# 3_MotorDriver.net
KiCad netlist of a schematic drawn in Altium Designer
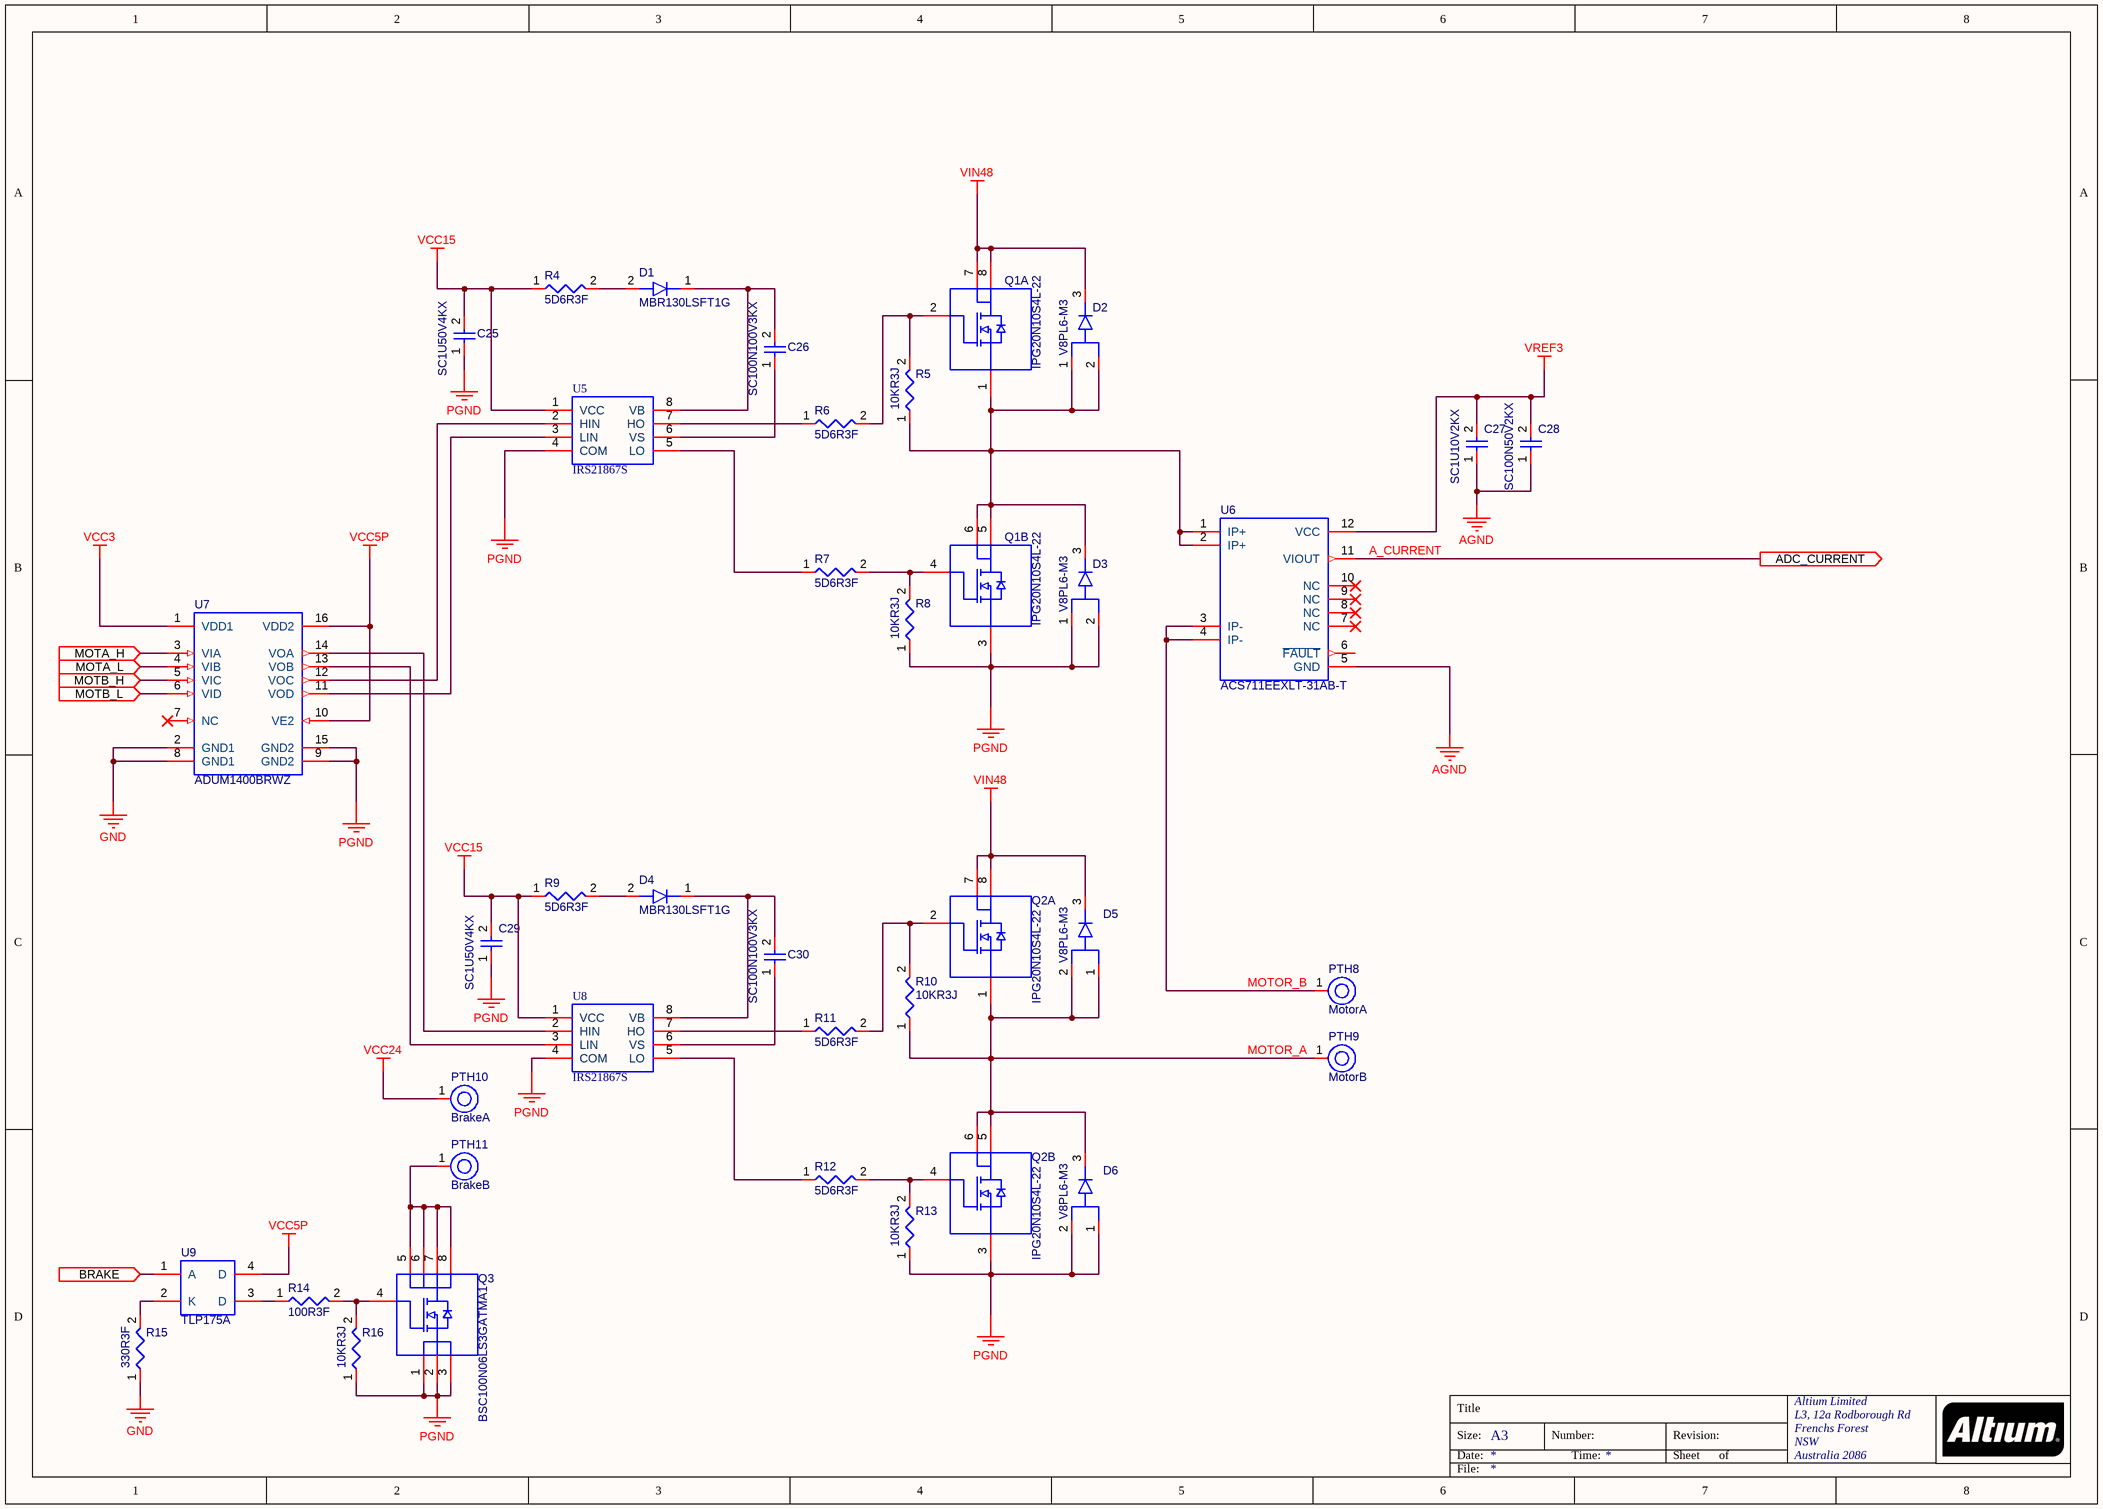
[diagram p0: 3_MotorDriver.SchDoc]

(export (version "E")
  (design (tool "Eeschema 10.0.6"))
  (components
    (comp (ref "C25")
      (value "SC1U50V4KX")
      (footprint "CAPC0805(2012)145_L")
      (description "CAP 1uF 50V ±10% 0805(1610 Metric) Thickness 1.2mm SMD")
      (libsource (lib "PUMAlib") (part "CAP(0805)1UF50V"))
    )
    (comp (ref "C26")
      (value "SC100N100V3KX")
      (footprint "CAPC0603(1608)100_L")
      (description "CAP 100nF 100V ±10% 0603(1608 Metric) Thickness 1mm SMD")
      (libsource (lib "PUMAlib") (part "CAP(0603)100nF100V"))
    )
    (comp (ref "C27")
      (value "SC1U10V2KX")
      (footprint "CAPC0402(1005)60_L")
      (description "CAP 1uF 10V ±10% 0402 (1005 Metric) Thickness 0.6mm SMD")
      (libsource (lib "Schlib") (part "CAP(0402)1UF10V"))
    )
    (comp (ref "C28")
      (value "SC100N50V2KX")
      (footprint "CAPC0402(1005)60_L")
      (description "CAP 100nF 50V ±10% 0402 (1005 Metric) Thickness 0.6mm SMD")
      (libsource (lib "Schlib") (part "CAP(0402)100nF50V"))
    )
    (comp (ref "C29")
      (value "SC1U50V4KX")
      (footprint "CAPC0805(2012)145_L")
      (description "CAP 1uF 50V ±10% 0805(1610 Metric) Thickness 1.2mm SMD")
      (libsource (lib "PUMAlib") (part "CAP(0805)1UF50V"))
    )
    (comp (ref "C30")
      (value "SC100N100V3KX")
      (footprint "CAPC0603(1608)100_L")
      (description "CAP 100nF 100V ±10% 0603(1608 Metric) Thickness 1mm SMD")
      (libsource (lib "PUMAlib") (part "CAP(0603)100nF100V"))
    )
    (comp (ref "D1")
      (value "MBR130LSFT1G")
      (footprint "SOD-123LF")
      (description "1А 30В [SOD-123FL]\r, RoHS, Tape and Reel")
      (fields (field (name "MANUFACTURER") "Rohm"))
      (libsource (lib "PUMAlib") (part "DIOD-MBR130"))
    )
    (comp (ref "D2")
      (value "V8PL6-M3")
      (footprint "DFN442P610X120-3L")
      (libsource (lib "PUMAlib") (part "VISH-V8PL6-M3"))
    )
    (comp (ref "D3")
      (value "V8PL6-M3")
      (footprint "DFN442P610X120-3L")
      (libsource (lib "PUMAlib") (part "VISH-V8PL6-M3"))
    )
    (comp (ref "D4")
      (value "MBR130LSFT1G")
      (footprint "SOD-123LF")
      (description "1А 30В [SOD-123FL]\r, RoHS, Tape and Reel")
      (fields (field (name "MANUFACTURER") "Rohm"))
      (libsource (lib "PUMAlib") (part "DIOD-MBR130"))
    )
    (comp (ref "D5")
      (value "V8PL6-M3")
      (footprint "DFN442P610X120-3L")
      (libsource (lib "PUMAlib") (part "VISH-V8PL6-M3"))
    )
    (comp (ref "D6")
      (value "V8PL6-M3")
      (footprint "DFN442P610X120-3L")
      (libsource (lib "PUMAlib") (part "VISH-V8PL6-M3"))
    )
    (comp (ref "PTH8")
      (value "MotorA")
      (footprint "POWERHOLE-LP")
      (description "1.2mm hole 2mm pad")
      (libsource (lib "PUMAlib") (part "PTH-1D2M"))
    )
    (comp (ref "PTH9")
      (value "MotorB")
      (footprint "POWERHOLE-LP")
      (description "1.2mm hole 2mm pad")
      (libsource (lib "PUMAlib") (part "PTH-1D2M"))
    )
    (comp (ref "PTH10")
      (value "BrakeA")
      (footprint "POWERHOLE-LP")
      (description "1.2mm hole 2mm pad")
      (libsource (lib "PUMAlib") (part "PTH-1D2M"))
    )
    (comp (ref "PTH11")
      (value "BrakeB")
      (footprint "POWERHOLE-LP")
      (description "1.2mm hole 2mm pad")
      (libsource (lib "PUMAlib") (part "PTH-1D2M"))
    )
    (comp (ref "Q1")
      (value "IPG20N10S4L-22")
      (footprint "PG-TDSON-8-4")
      (description "OptiMOS™-T2 Power-Transistor V DS 100 V\r\nR DS(on) max 22\r\nID 20 A")
      (libsource (lib "PUMAlib") (part "INF_IPG20N06S4L-26"))
    )
    (comp (ref "Q2")
      (value "IPG20N10S4L-22")
      (footprint "PG-TDSON-8-4")
      (description "OptiMOS™-T2 Power-Transistor V DS 100 V\r\nR DS(on) max 22\r\nID 20 A")
      (libsource (lib "PUMAlib") (part "INF_IPG20N06S4L-26"))
    )
    (comp (ref "Q3")
      (value "BSC100N06LS3GATMA1")
      (footprint "PG-TDSON-8-1")
      (description "100 V N-Channel NexFET™ Power MOSFETs")
      (libsource (lib "PUMAlib") (part "NEMOS-BSC100N06L"))
    )
    (comp (ref "R4")
      (value "5D6R3F")
      (footprint "RESC0603(1608)_L")
      (description "5.6R 0.1W 1% 0603 (1608 Metric)  SMD")
      (libsource (lib "PUMAlib") (part "RES0(0603)_5R6"))
    )
    (comp (ref "R5")
      (value "10KR3J")
      (footprint "RESC0603(1608)_L")
      (description "10K 0.1W 5% 0603 (1608 Metric)  SMD")
      (libsource (lib "PUMAlib") (part "RES0(0603)_10K"))
    )
    (comp (ref "R6")
      (value "5D6R3F")
      (footprint "RESC0603(1608)_L")
      (description "5.6R 0.1W 1% 0603 (1608 Metric)  SMD")
      (libsource (lib "PUMAlib") (part "RES0(0603)_5R6"))
    )
    (comp (ref "R7")
      (value "5D6R3F")
      (footprint "RESC0603(1608)_L")
      (description "5.6R 0.1W 1% 0603 (1608 Metric)  SMD")
      (libsource (lib "PUMAlib") (part "RES0(0603)_5R6"))
    )
    (comp (ref "R8")
      (value "10KR3J")
      (footprint "RESC0603(1608)_L")
      (description "10K 0.1W 5% 0603 (1608 Metric)  SMD")
      (libsource (lib "PUMAlib") (part "RES0(0603)_10K"))
    )
    (comp (ref "R9")
      (value "5D6R3F")
      (footprint "RESC0603(1608)_L")
      (description "5.6R 0.1W 1% 0603 (1608 Metric)  SMD")
      (libsource (lib "PUMAlib") (part "RES0(0603)_5R6"))
    )
    (comp (ref "R10")
      (value "10KR3J")
      (footprint "RESC0603(1608)_L")
      (description "10K 0.1W 5% 0603 (1608 Metric)  SMD")
      (libsource (lib "PUMAlib") (part "RES0(0603)_10K"))
    )
    (comp (ref "R11")
      (value "5D6R3F")
      (footprint "RESC0603(1608)_L")
      (description "5.6R 0.1W 1% 0603 (1608 Metric)  SMD")
      (libsource (lib "PUMAlib") (part "RES0(0603)_5R6"))
    )
    (comp (ref "R12")
      (value "5D6R3F")
      (footprint "RESC0603(1608)_L")
      (description "5.6R 0.1W 1% 0603 (1608 Metric)  SMD")
      (libsource (lib "PUMAlib") (part "RES0(0603)_5R6"))
    )
    (comp (ref "R13")
      (value "10KR3J")
      (footprint "RESC0603(1608)_L")
      (description "10K 0.1W 5% 0603 (1608 Metric)  SMD")
      (libsource (lib "PUMAlib") (part "RES0(0603)_10K"))
    )
    (comp (ref "R14")
      (value "100R3F")
      (footprint "RESC0603(1608)_L")
      (description "100R 0.1W 1% 0603 (1608 Metric)  SMD")
      (libsource (lib "PUMAlib") (part "RES0(0603)_100R"))
    )
    (comp (ref "R15")
      (value "330R3F")
      (footprint "RESC0603(1608)_L")
      (description "330R 0.1W 1% 0603 (1608 Metric)  SMD")
      (libsource (lib "PUMAlib") (part "RES0(0603)_330R"))
    )
    (comp (ref "R16")
      (value "10KR3J")
      (footprint "RESC0603(1608)_L")
      (description "10K 0.1W 5% 0603 (1608 Metric)  SMD")
      (libsource (lib "PUMAlib") (part "RES0(0603)_10K"))
    )
    (comp (ref "U5")
      (value "IRS21867S")
      (footprint "SOIC127P600X175-8L")
      (libsource (lib "PUMAlib") (part "MOSDRV_IRS21867S"))
    )
    (comp (ref "U6")
      (value "ACS711EEXLT-31AB-T")
      (footprint "ACS711EX")
      (description "High Accuracy, Hall-Effect Based Current Sensor\r\nIC in High Isolation QFN Package")
      (libsource (lib "PUMAlib") (part "ACS711EX"))
    )
    (comp (ref "U7")
      (value "ADUM1400BRWZ")
      (footprint "SOIC127P1030X265-16L")
      (description "ISOLATOR 4ch in")
      (libsource (lib "PUMAlib") (part "ISOL-ADUM1400"))
    )
    (comp (ref "U8")
      (value "IRS21867S")
      (footprint "SOIC127P600X175-8L")
      (libsource (lib "PUMAlib") (part "MOSDRV_IRS21867S"))
    )
    (comp (ref "U9")
      (value "TLP175A")
      (footprint "SOP254P700X220-4L")
      (libsource (lib "PUMAlib") (part "OPTO-TLP175A"))
    )
  )
  (nets
    (net (code "1") (name "/A_CURRENT") (class "Default")
      (node (ref "U6") (pin "11") (pinfunction "VIOUT_11") (pintype "output"))
    )
    (net (code "2") (name "/BRAKE") (class "Default")
      (node (ref "U9") (pin "1") (pinfunction "A_1") (pintype "passive"))
    )
    (net (code "3") (name "/MOTA_H") (class "Default")
      (node (ref "U7") (pin "3") (pinfunction "VIA_3") (pintype "input"))
    )
    (net (code "4") (name "/MOTA_L") (class "Default")
      (node (ref "U7") (pin "4") (pinfunction "VIB_4") (pintype "input"))
    )
    (net (code "5") (name "/MOTB_H") (class "Default")
      (node (ref "U7") (pin "5") (pinfunction "VIC_5") (pintype "input"))
    )
    (net (code "6") (name "/MOTB_L") (class "Default")
      (node (ref "U7") (pin "6") (pinfunction "VID_6") (pintype "input"))
    )
    (net (code "7") (name "/MOTOR_A") (class "Default")
      (node (ref "D5") (pin "1") (pinfunction "A1_1") (pintype "passive"))
      (node (ref "D5") (pin "2") (pinfunction "A2_2") (pintype "passive"))
      (node (ref "D6") (pin "3") (pinfunction "K_3") (pintype "passive"))
      (node (ref "PTH9") (pin "1") (pinfunction "H1_1") (pintype "passive"))
      (node (ref "Q2") (pin "1") (pintype "passive"))
      (node (ref "Q2") (pin "5") (pintype "open_collector"))
      (node (ref "Q2") (pin "6") (pintype "open_collector"))
      (node (ref "R10") (pin "1") (pinfunction "1_1") (pintype "passive"))
    )
    (net (code "8") (name "/MOTOR_B") (class "Default")
      (node (ref "PTH8") (pin "1") (pinfunction "H1_1") (pintype "passive"))
      (node (ref "U6") (pin "3") (pinfunction "IP-_3") (pintype "passive"))
      (node (ref "U6") (pin "4") (pinfunction "IP-_4") (pintype "passive"))
    )
    (net (code "9") (name "AGND") (class "Default")
      (node (ref "C27") (pin "1") (pinfunction "1_1") (pintype "passive"))
      (node (ref "C28") (pin "1") (pinfunction "1_1") (pintype "passive"))
      (node (ref "U6") (pin "5") (pinfunction "GND_5") (pintype "power_in"))
    )
    (net (code "10") (name "GND") (class "Default")
      (node (ref "R15") (pin "1") (pinfunction "1_1") (pintype "passive"))
      (node (ref "U7") (pin "2") (pinfunction "GND1_2") (pintype "power_in"))
      (node (ref "U7") (pin "8") (pinfunction "GND1_8") (pintype "power_in"))
    )
    (net (code "11") (name "Net-(D1-A)") (class "Default")
      (node (ref "D1") (pin "2") (pinfunction "A_2") (pintype "passive"))
      (node (ref "R4") (pin "2") (pinfunction "2_2") (pintype "passive"))
    )
    (net (code "12") (name "Net-(D1-K)") (class "Default")
      (node (ref "C26") (pin "2") (pinfunction "2_2") (pintype "passive"))
      (node (ref "D1") (pin "1") (pinfunction "K_1") (pintype "passive"))
      (node (ref "U5") (pin "8") (pinfunction "VB_8") (pintype "passive"))
    )
    (net (code "13") (name "Net-(D2-A1)") (class "Default")
      (node (ref "D2") (pin "1") (pinfunction "A1_1") (pintype "passive"))
      (node (ref "D2") (pin "2") (pinfunction "A2_2") (pintype "passive"))
      (node (ref "D3") (pin "3") (pinfunction "K_3") (pintype "passive"))
      (node (ref "Q1") (pin "1") (pintype "passive"))
      (node (ref "Q1") (pin "5") (pintype "open_collector"))
      (node (ref "Q1") (pin "6") (pintype "open_collector"))
      (node (ref "R5") (pin "1") (pinfunction "1_1") (pintype "passive"))
      (node (ref "U6") (pin "1") (pinfunction "IP+_1") (pintype "passive"))
      (node (ref "U6") (pin "2") (pinfunction "IP+_2") (pintype "passive"))
    )
    (net (code "14") (name "Net-(D4-A)") (class "Default")
      (node (ref "D4") (pin "2") (pinfunction "A_2") (pintype "passive"))
      (node (ref "R9") (pin "2") (pinfunction "2_2") (pintype "passive"))
    )
    (net (code "15") (name "Net-(D4-K)") (class "Default")
      (node (ref "C30") (pin "2") (pinfunction "2_2") (pintype "passive"))
      (node (ref "D4") (pin "1") (pinfunction "K_1") (pintype "passive"))
      (node (ref "U8") (pin "8") (pinfunction "VB_8") (pintype "passive"))
    )
    (net (code "16") (name "Net-(PTH11-H1)") (class "Default")
      (node (ref "PTH11") (pin "1") (pinfunction "H1_1") (pintype "passive"))
      (node (ref "Q3") (pin "5") (pintype "open_collector"))
      (node (ref "Q3") (pin "6") (pintype "open_collector"))
      (node (ref "Q3") (pin "7") (pintype "open_collector"))
      (node (ref "Q3") (pin "8") (pintype "open_collector"))
    )
    (net (code "17") (name "Net-(Q1-Pad2)") (class "Default")
      (node (ref "Q1") (pin "2") (pintype "open_collector"))
      (node (ref "R5") (pin "2") (pinfunction "2_2") (pintype "passive"))
      (node (ref "R6") (pin "2") (pinfunction "2_2") (pintype "passive"))
    )
    (net (code "18") (name "Net-(Q1-Pad4)") (class "Default")
      (node (ref "Q1") (pin "4") (pintype "open_collector"))
      (node (ref "R7") (pin "2") (pinfunction "2_2") (pintype "passive"))
      (node (ref "R8") (pin "2") (pinfunction "2_2") (pintype "passive"))
    )
    (net (code "19") (name "Net-(Q2-Pad2)") (class "Default")
      (node (ref "Q2") (pin "2") (pintype "open_collector"))
      (node (ref "R10") (pin "2") (pinfunction "2_2") (pintype "passive"))
      (node (ref "R11") (pin "2") (pinfunction "2_2") (pintype "passive"))
    )
    (net (code "20") (name "Net-(Q2-Pad4)") (class "Default")
      (node (ref "Q2") (pin "4") (pintype "open_collector"))
      (node (ref "R12") (pin "2") (pinfunction "2_2") (pintype "passive"))
      (node (ref "R13") (pin "2") (pinfunction "2_2") (pintype "passive"))
    )
    (net (code "21") (name "Net-(Q3-Pad4)") (class "Default")
      (node (ref "Q3") (pin "4") (pintype "open_collector"))
      (node (ref "R14") (pin "2") (pinfunction "2_2") (pintype "passive"))
      (node (ref "R16") (pin "2") (pinfunction "2_2") (pintype "passive"))
    )
    (net (code "22") (name "Net-(R14-Pad1)") (class "Default")
      (node (ref "R14") (pin "1") (pinfunction "1_1") (pintype "passive"))
      (node (ref "U9") (pin "3") (pinfunction "D_3") (pintype "passive"))
    )
    (net (code "23") (name "Net-(U5-HIN)") (class "Default")
      (node (ref "U5") (pin "2") (pinfunction "HIN_2") (pintype "passive"))
      (node (ref "U7") (pin "12") (pinfunction "VOC_12") (pintype "output"))
    )
    (net (code "24") (name "Net-(U5-HO)") (class "Default")
      (node (ref "R6") (pin "1") (pinfunction "1_1") (pintype "passive"))
      (node (ref "U5") (pin "7") (pinfunction "HO_7") (pintype "passive"))
    )
    (net (code "25") (name "Net-(U5-LIN)") (class "Default")
      (node (ref "U5") (pin "3") (pinfunction "LIN_3") (pintype "passive"))
      (node (ref "U7") (pin "11") (pinfunction "VOD_11") (pintype "output"))
    )
    (net (code "26") (name "Net-(U5-LO)") (class "Default")
      (node (ref "R7") (pin "1") (pinfunction "1_1") (pintype "passive"))
      (node (ref "U5") (pin "5") (pinfunction "LO_5") (pintype "passive"))
    )
    (net (code "27") (name "Net-(U5-VS)") (class "Default")
      (node (ref "C26") (pin "1") (pinfunction "1_1") (pintype "passive"))
      (node (ref "U5") (pin "6") (pinfunction "VS_6") (pintype "passive"))
    )
    (net (code "28") (name "Net-(U7-VOA)") (class "Default")
      (node (ref "U7") (pin "14") (pinfunction "VOA_14") (pintype "output"))
      (node (ref "U8") (pin "2") (pinfunction "HIN_2") (pintype "passive"))
    )
    (net (code "29") (name "Net-(U7-VOB)") (class "Default")
      (node (ref "U7") (pin "13") (pinfunction "VOB_13") (pintype "output"))
      (node (ref "U8") (pin "3") (pinfunction "LIN_3") (pintype "passive"))
    )
    (net (code "30") (name "Net-(U8-HO)") (class "Default")
      (node (ref "R11") (pin "1") (pinfunction "1_1") (pintype "passive"))
      (node (ref "U8") (pin "7") (pinfunction "HO_7") (pintype "passive"))
    )
    (net (code "31") (name "Net-(U8-LO)") (class "Default")
      (node (ref "R12") (pin "1") (pinfunction "1_1") (pintype "passive"))
      (node (ref "U8") (pin "5") (pinfunction "LO_5") (pintype "passive"))
    )
    (net (code "32") (name "Net-(U8-VS)") (class "Default")
      (node (ref "C30") (pin "1") (pinfunction "1_1") (pintype "passive"))
      (node (ref "U8") (pin "6") (pinfunction "VS_6") (pintype "passive"))
    )
    (net (code "33") (name "Net-(U9-K)") (class "Default")
      (node (ref "R15") (pin "2") (pinfunction "2_2") (pintype "passive"))
      (node (ref "U9") (pin "2") (pinfunction "K_2") (pintype "passive"))
    )
    (net (code "34") (name "PGND") (class "Default")
      (node (ref "C25") (pin "1") (pinfunction "1_1") (pintype "passive"))
      (node (ref "C29") (pin "1") (pinfunction "1_1") (pintype "passive"))
      (node (ref "D3") (pin "1") (pinfunction "A1_1") (pintype "passive"))
      (node (ref "D3") (pin "2") (pinfunction "A2_2") (pintype "passive"))
      (node (ref "D6") (pin "1") (pinfunction "A1_1") (pintype "passive"))
      (node (ref "D6") (pin "2") (pinfunction "A2_2") (pintype "passive"))
      (node (ref "Q1") (pin "3") (pintype "passive"))
      (node (ref "Q2") (pin "3") (pintype "passive"))
      (node (ref "Q3") (pin "1") (pintype "passive"))
      (node (ref "Q3") (pin "2") (pintype "passive"))
      (node (ref "Q3") (pin "3") (pintype "passive"))
      (node (ref "R13") (pin "1") (pinfunction "1_1") (pintype "passive"))
      (node (ref "R16") (pin "1") (pinfunction "1_1") (pintype "passive"))
      (node (ref "R8") (pin "1") (pinfunction "1_1") (pintype "passive"))
      (node (ref "U5") (pin "4") (pinfunction "COM_4") (pintype "passive"))
      (node (ref "U7") (pin "15") (pinfunction "GND2_15") (pintype "power_in"))
      (node (ref "U7") (pin "9") (pinfunction "GND2_9") (pintype "power_in"))
      (node (ref "U8") (pin "4") (pinfunction "COM_4") (pintype "passive"))
    )
    (net (code "35") (name "VCC3") (class "Default")
      (node (ref "U7") (pin "1") (pinfunction "VDD1_1") (pintype "power_in"))
    )
    (net (code "36") (name "VCC5P") (class "Default")
      (node (ref "U7") (pin "10") (pinfunction "VE2_10") (pintype "input"))
      (node (ref "U7") (pin "16") (pinfunction "VDD2_16") (pintype "power_in"))
      (node (ref "U9") (pin "4") (pinfunction "D_4") (pintype "passive"))
    )
    (net (code "37") (name "VCC15") (class "Default")
      (node (ref "C25") (pin "2") (pinfunction "2_2") (pintype "passive"))
      (node (ref "C29") (pin "2") (pinfunction "2_2") (pintype "passive"))
      (node (ref "R4") (pin "1") (pinfunction "1_1") (pintype "passive"))
      (node (ref "R9") (pin "1") (pinfunction "1_1") (pintype "passive"))
      (node (ref "U5") (pin "1") (pinfunction "VCC_1") (pintype "passive"))
      (node (ref "U8") (pin "1") (pinfunction "VCC_1") (pintype "passive"))
    )
    (net (code "38") (name "VCC24") (class "Default")
      (node (ref "PTH10") (pin "1") (pinfunction "H1_1") (pintype "passive"))
    )
    (net (code "39") (name "VIN48") (class "Default")
      (node (ref "D2") (pin "3") (pinfunction "K_3") (pintype "passive"))
      (node (ref "D5") (pin "3") (pinfunction "K_3") (pintype "passive"))
      (node (ref "Q1") (pin "7") (pintype "open_collector"))
      (node (ref "Q1") (pin "8") (pintype "open_collector"))
      (node (ref "Q2") (pin "7") (pintype "open_collector"))
      (node (ref "Q2") (pin "8") (pintype "open_collector"))
    )
    (net (code "40") (name "VREF3") (class "Default")
      (node (ref "C27") (pin "2") (pinfunction "2_2") (pintype "passive"))
      (node (ref "C28") (pin "2") (pinfunction "2_2") (pintype "passive"))
      (node (ref "U6") (pin "12") (pinfunction "VCC_12") (pintype "power_in"))
    )
    (net (code "41") (name "unconnected-(U6-NC-Pad7)") (class "Default")
      (node (ref "U6") (pin "7") (pinfunction "NC_7") (pintype "passive+no_connect"))
    )
    (net (code "42") (name "unconnected-(U6-NC-Pad8)") (class "Default")
      (node (ref "U6") (pin "8") (pinfunction "NC_8") (pintype "passive+no_connect"))
    )
    (net (code "43") (name "unconnected-(U6-NC-Pad9)") (class "Default")
      (node (ref "U6") (pin "9") (pinfunction "NC_9") (pintype "passive+no_connect"))
    )
    (net (code "44") (name "unconnected-(U6-NC-Pad10)") (class "Default")
      (node (ref "U6") (pin "10") (pinfunction "NC_10") (pintype "passive+no_connect"))
    )
    (net (code "45") (name "unconnected-(U6-~{FAULT}-Pad6)") (class "Default")
      (node (ref "U6") (pin "6") (pinfunction "~{FAULT}_6") (pintype "output"))
    )
    (net (code "46") (name "unconnected-(U7-NC-Pad7)") (class "Default")
      (node (ref "U7") (pin "7") (pinfunction "NC_7") (pintype "input+no_connect"))
    )
  )
)
